# ESO_SENIOR_DESIGN.net
KiCad netlist of a schematic drawn in EAGLE
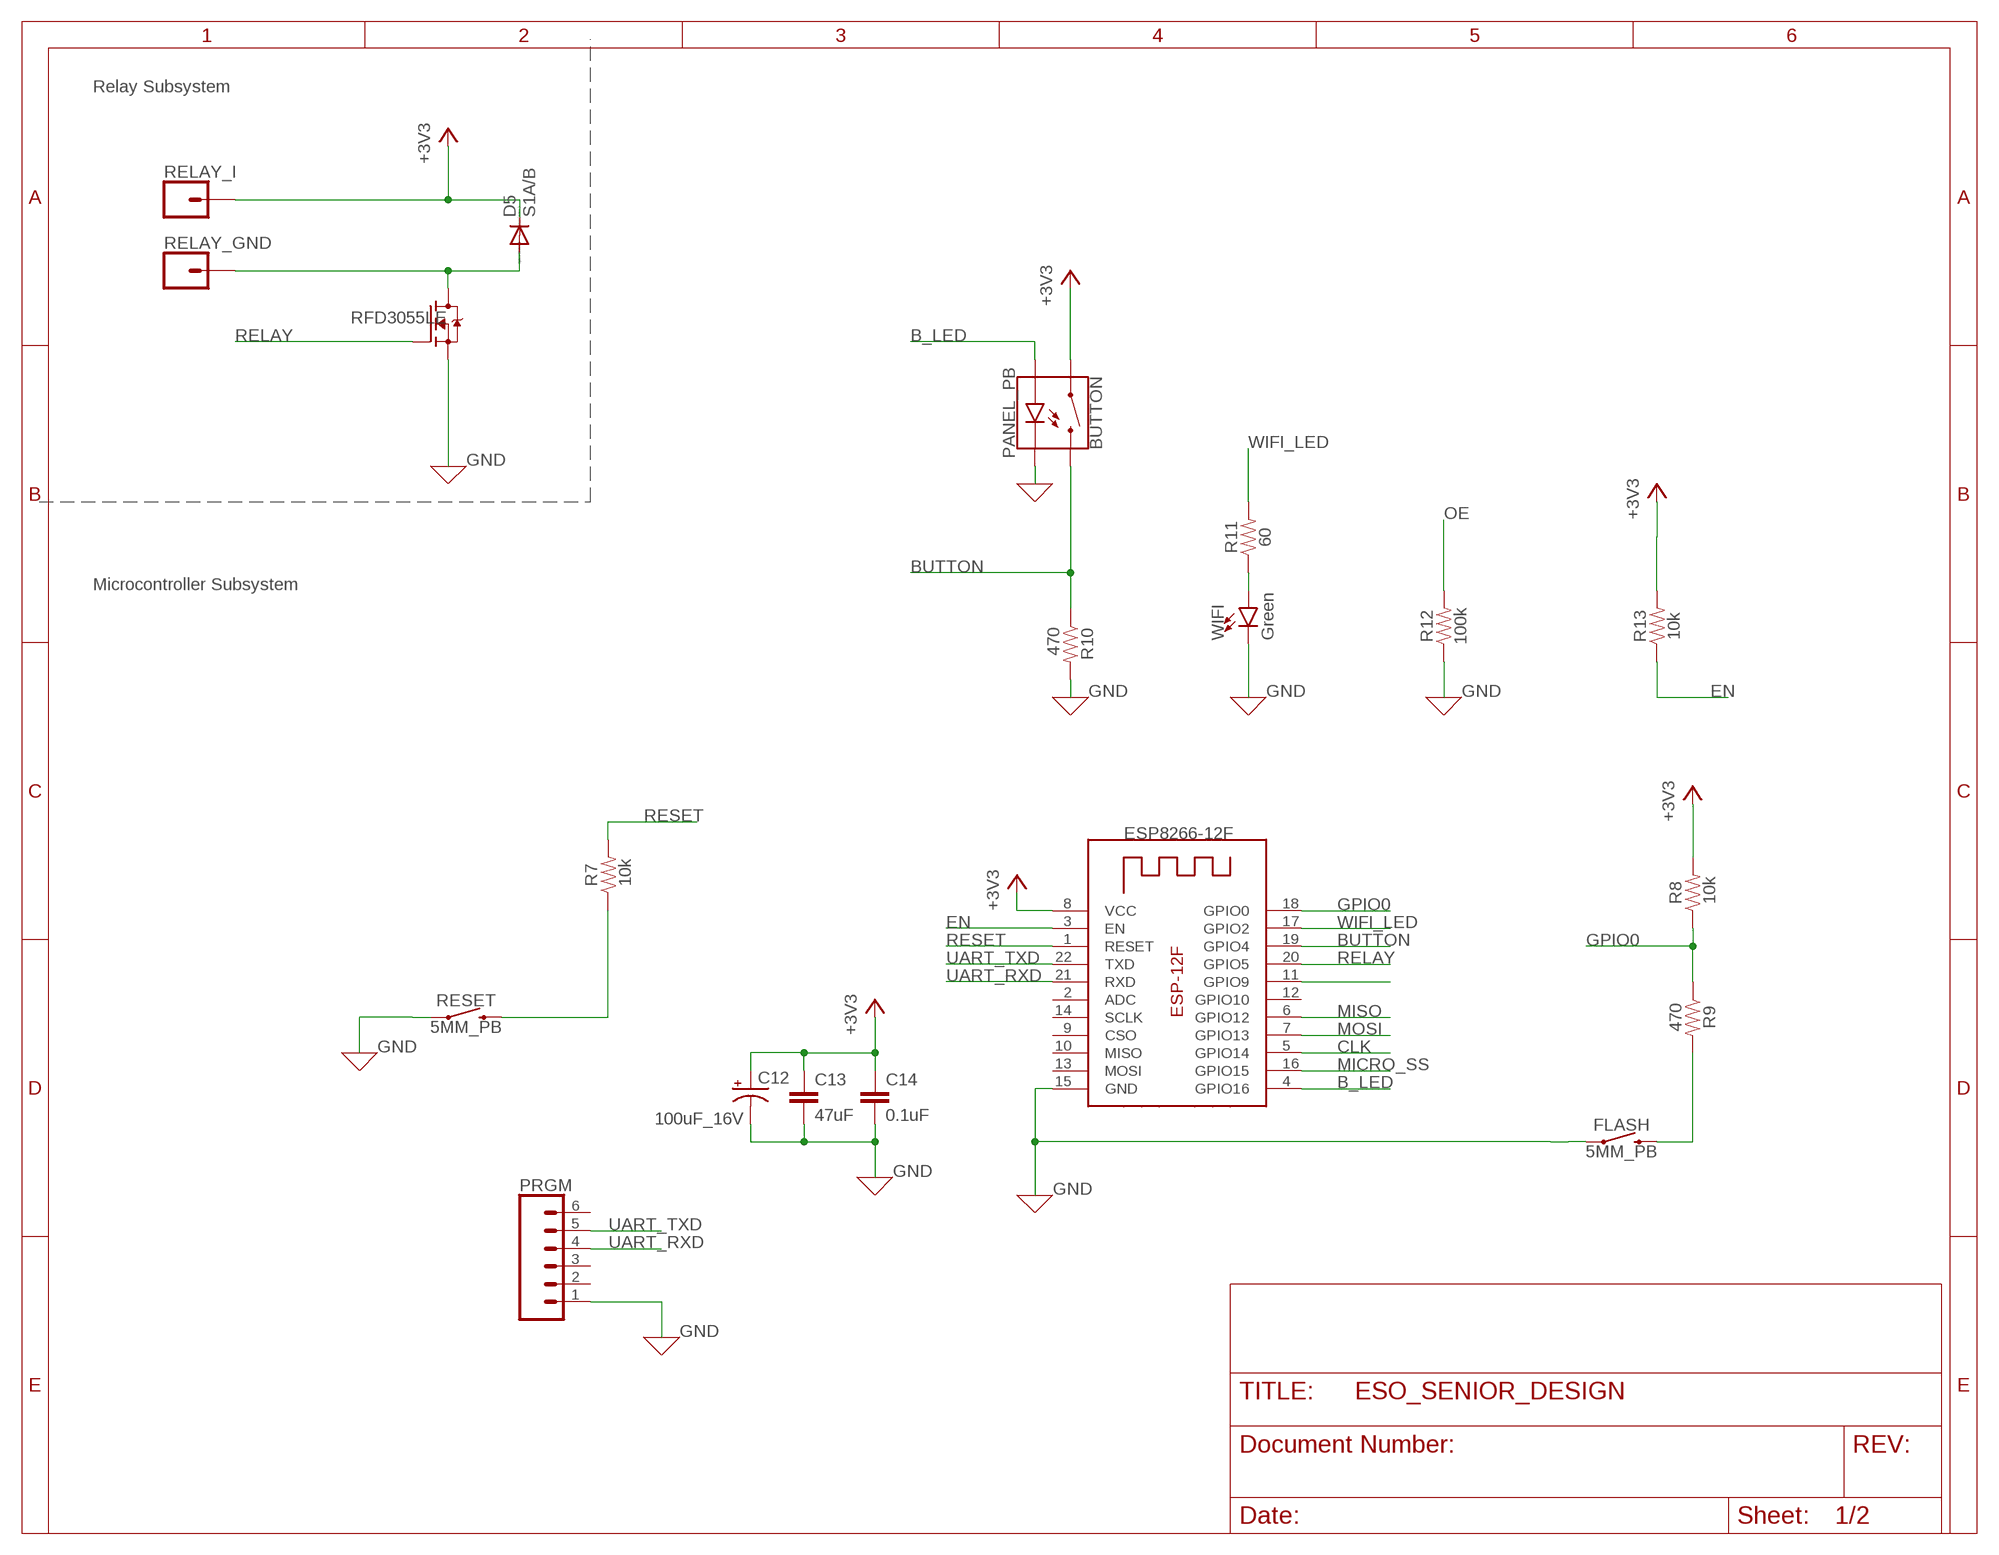
[diagram p0: schematic, sheet 1, part 1 of 2]
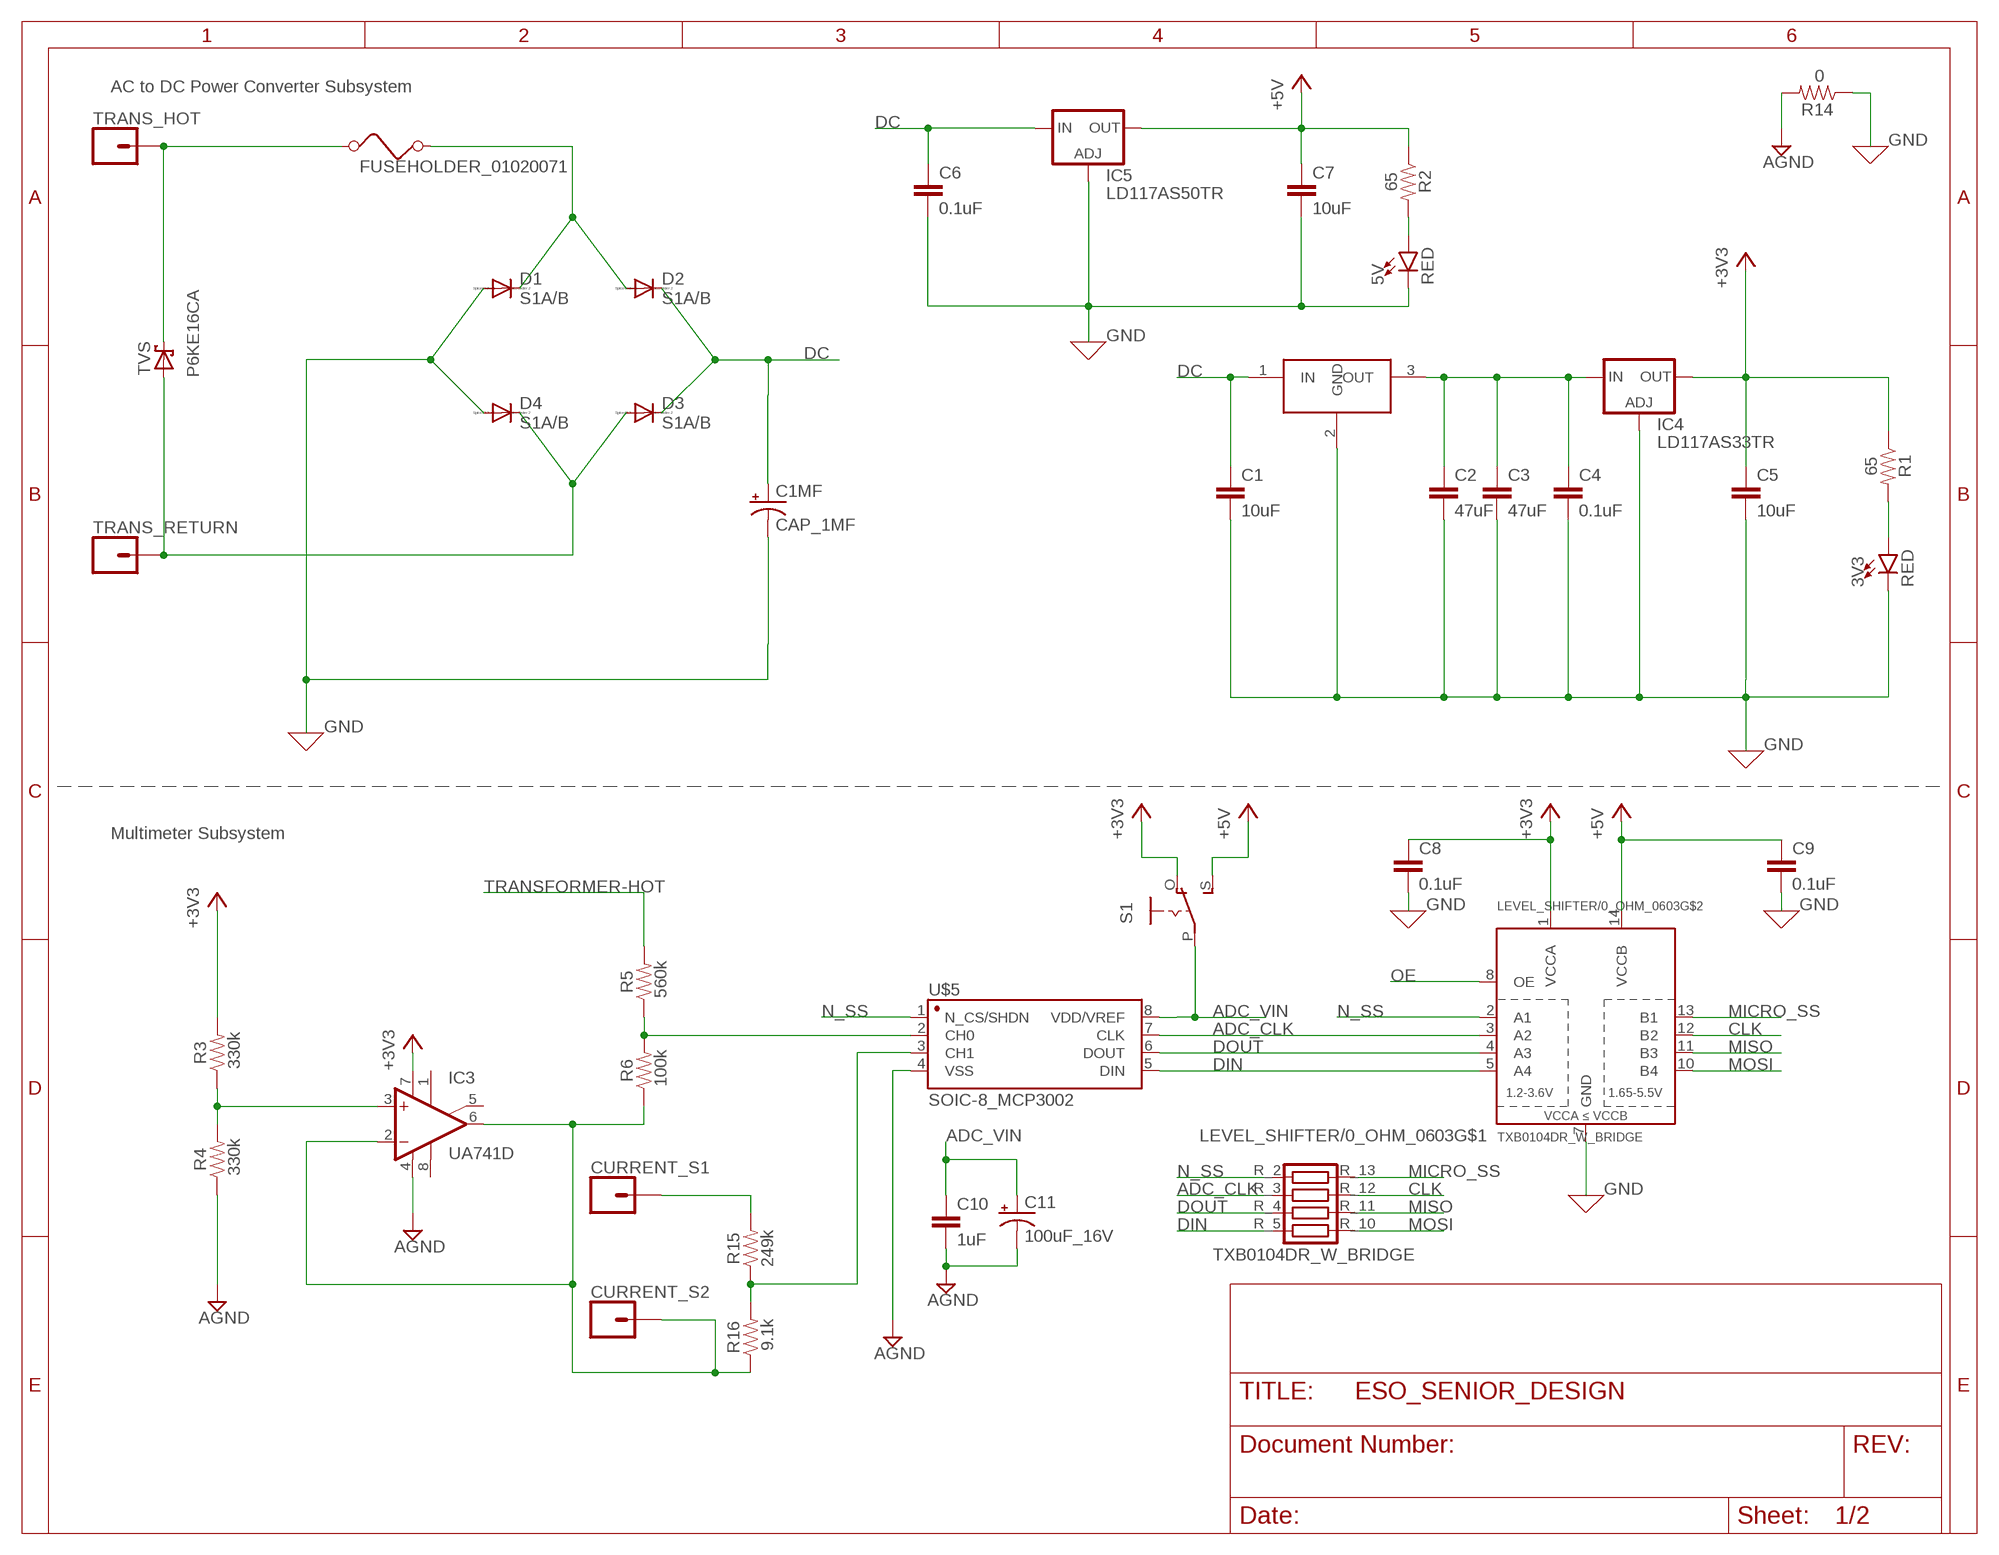
[diagram p1: schematic, sheet 1, part 2 of 2]

(export (version "E")
  (design (tool "Eeschema 10.0.6"))
  (components
    (comp (ref "3V3")
      (value "RED")
      (footprint "eagle-import:LED-1206")
      (libsource (lib "eagle-import") (part "LED1206"))
    )
    (comp (ref "5V")
      (value "RED")
      (footprint "eagle-import:LED-1206")
      (libsource (lib "eagle-import") (part "LED1206"))
    )
    (comp (ref "12F")
      (value "ESP-12F")
      (footprint "eagle-import:ESP-12F")
      (libsource (lib "eagle-import") (part "ESP-12F"))
    )
    (comp (ref "BUTTON")
      (value "PANEL_PB")
      (footprint "eagle-import:PANEL_PB")
      (libsource (lib "eagle-import") (part "PANEL_PB"))
    )
    (comp (ref "C1")
      (value "10uF")
      (footprint "eagle-import:C0805")
      (libsource (lib "eagle-import") (part "C-EUC0805"))
    )
    (comp (ref "C1MF")
      (value "CAP_1MF")
      (footprint "eagle-import:PANASONIC_H13")
      (libsource (lib "eagle-import") (part "CAP_1MF"))
    )
    (comp (ref "C2")
      (value "47uF")
      (footprint "eagle-import:C0805")
      (libsource (lib "eagle-import") (part "C-EUC0805"))
    )
    (comp (ref "C3")
      (value "47uF")
      (footprint "eagle-import:C0805")
      (libsource (lib "eagle-import") (part "C-EUC0805"))
    )
    (comp (ref "C4")
      (value "0.1uF")
      (footprint "eagle-import:C0805")
      (libsource (lib "eagle-import") (part "C-EUC0805"))
    )
    (comp (ref "C5")
      (value "10uF")
      (footprint "eagle-import:C0805")
      (libsource (lib "eagle-import") (part "C-EUC0805"))
    )
    (comp (ref "C6")
      (value "0.1uF")
      (footprint "eagle-import:C0805")
      (libsource (lib "eagle-import") (part "C-EUC0805"))
    )
    (comp (ref "C7")
      (value "10uF")
      (footprint "eagle-import:C0805")
      (libsource (lib "eagle-import") (part "C-EUC0805"))
    )
    (comp (ref "C8")
      (value "0.1uF")
      (footprint "eagle-import:C0805")
      (libsource (lib "eagle-import") (part "C-EUC0805"))
    )
    (comp (ref "C9")
      (value "0.1uF")
      (footprint "eagle-import:C0805")
      (libsource (lib "eagle-import") (part "C-EUC0805"))
    )
    (comp (ref "C10")
      (value "1uF")
      (footprint "eagle-import:C0805")
      (libsource (lib "eagle-import") (part "C-EUC0805"))
    )
    (comp (ref "C11")
      (value "100uF_16V")
      (footprint "eagle-import:PANASONIC_C")
      (libsource (lib "eagle-import") (part "CPOL-USC"))
    )
    (comp (ref "C12")
      (value "100uF_16V")
      (footprint "eagle-import:PANASONIC_C")
      (libsource (lib "eagle-import") (part "CPOL-USC"))
    )
    (comp (ref "C13")
      (value "47uF")
      (footprint "eagle-import:C0805")
      (libsource (lib "eagle-import") (part "C-EUC0805"))
    )
    (comp (ref "C14")
      (value "0.1uF")
      (footprint "eagle-import:C0805")
      (libsource (lib "eagle-import") (part "C-EUC0805"))
    )
    (comp (ref "CURRENT_S1")
      (value "CONN_01")
      (footprint "eagle-import:1X01")
      (libsource (lib "eagle-import") (part "CONN_01"))
    )
    (comp (ref "CURRENT_S2")
      (value "CONN_01")
      (footprint "eagle-import:1X01")
      (libsource (lib "eagle-import") (part "CONN_01"))
    )
    (comp (ref "D1")
      (value "S1A/B")
      (footprint "eagle-import:SMB")
      (libsource (lib "eagle-import") (part "DIODE-SMB"))
    )
    (comp (ref "D2")
      (value "S1A/B")
      (footprint "eagle-import:SMB")
      (libsource (lib "eagle-import") (part "DIODE-SMB"))
    )
    (comp (ref "D3")
      (value "S1A/B")
      (footprint "eagle-import:SMB")
      (libsource (lib "eagle-import") (part "DIODE-SMB"))
    )
    (comp (ref "D4")
      (value "S1A/B")
      (footprint "eagle-import:SMB")
      (libsource (lib "eagle-import") (part "DIODE-SMB"))
    )
    (comp (ref "D5")
      (value "S1A/B")
      (footprint "eagle-import:SMB")
      (libsource (lib "eagle-import") (part "DIODE-SMB"))
    )
    (comp (ref "FLASH")
      (value "5MM_PB")
      (footprint "eagle-import:TACTILE_SWITCH_SMD_5MM")
      (libsource (lib "eagle-import") (part "5MM_PB"))
    )
    (comp (ref "IC3")
      (value "UA741D")
      (footprint "eagle-import:SO08")
      (libsource (lib "eagle-import") (part "741DUA"))
    )
    (comp (ref "IC4")
      (value "LD117AS33TR")
      (footprint "eagle-import:SOT223")
      (libsource (lib "eagle-import") (part "LD117A?S33TR"))
    )
    (comp (ref "IC5")
      (value "LD117AS50TR")
      (footprint "eagle-import:SOT223")
      (libsource (lib "eagle-import") (part "LD117A?S50TR"))
    )
    (comp (ref "LEVEL_SHIFTER/0_OHM_0603")
      (value "TXB0104DR_W_BRIDGE")
      (footprint "eagle-import:SO14")
      (libsource (lib "eagle-import") (part "TXB0104DR_W_BRIDGE"))
    )
    (comp (ref "PRGM")
      (value "CONN_06NO_SILK_FEMALE_PTH")
      (footprint "eagle-import:1X06_NO_SILK")
      (libsource (lib "eagle-import") (part "CONN_06NO_SILK_FEMALE_PTH"))
    )
    (comp (ref "Q$1")
      (value "RFD3055LE")
      (footprint "eagle-import:TO92-SGD")
      (libsource (lib "eagle-import") (part "RFD3055LE"))
    )
    (comp (ref "R1")
      (value "65")
      (footprint "eagle-import:0805")
      (libsource (lib "eagle-import") (part "RESISTOR0805"))
    )
    (comp (ref "R2")
      (value "65")
      (footprint "eagle-import:0805")
      (libsource (lib "eagle-import") (part "RESISTOR0805"))
    )
    (comp (ref "R3")
      (value "330k")
      (footprint "eagle-import:0805")
      (libsource (lib "eagle-import") (part "RESISTOR0805"))
    )
    (comp (ref "R4")
      (value "330k")
      (footprint "eagle-import:0805")
      (libsource (lib "eagle-import") (part "RESISTOR0805"))
    )
    (comp (ref "R5")
      (value "560k")
      (footprint "eagle-import:0805")
      (libsource (lib "eagle-import") (part "RESISTOR0805"))
    )
    (comp (ref "R6")
      (value "100k")
      (footprint "eagle-import:0805")
      (libsource (lib "eagle-import") (part "RESISTOR0805"))
    )
    (comp (ref "R7")
      (value "10k")
      (footprint "eagle-import:0805")
      (libsource (lib "eagle-import") (part "RESISTOR0805"))
    )
    (comp (ref "R8")
      (value "10k")
      (footprint "eagle-import:0805")
      (libsource (lib "eagle-import") (part "RESISTOR0805"))
    )
    (comp (ref "R9")
      (value "470")
      (footprint "eagle-import:0805")
      (libsource (lib "eagle-import") (part "RESISTOR0805"))
    )
    (comp (ref "R10")
      (value "470")
      (footprint "eagle-import:0805")
      (libsource (lib "eagle-import") (part "RESISTOR0805"))
    )
    (comp (ref "R11")
      (value "60")
      (footprint "eagle-import:0805")
      (libsource (lib "eagle-import") (part "RESISTOR0805"))
    )
    (comp (ref "R12")
      (value "100k")
      (footprint "eagle-import:0805")
      (libsource (lib "eagle-import") (part "RESISTOR0805"))
    )
    (comp (ref "R13")
      (value "10k")
      (footprint "eagle-import:0805")
      (libsource (lib "eagle-import") (part "RESISTOR0805"))
    )
    (comp (ref "R14")
      (value "0")
      (footprint "eagle-import:0805")
      (libsource (lib "eagle-import") (part "RESISTOR0805"))
    )
    (comp (ref "R15")
      (value "249k")
      (footprint "eagle-import:0805")
      (libsource (lib "eagle-import") (part "RESISTOR0805"))
    )
    (comp (ref "R16")
      (value "9.1k")
      (footprint "eagle-import:0805")
      (libsource (lib "eagle-import") (part "RESISTOR0805"))
    )
    (comp (ref "RELAY_GND")
      (value "CONN_01")
      (footprint "eagle-import:1X01")
      (libsource (lib "eagle-import") (part "CONN_01"))
    )
    (comp (ref "RELAY_I")
      (value "CONN_01")
      (footprint "eagle-import:1X01")
      (libsource (lib "eagle-import") (part "CONN_01"))
    )
    (comp (ref "RESET")
      (value "5MM_PB")
      (footprint "eagle-import:TACTILE_SWITCH_SMD_5MM")
      (libsource (lib "eagle-import") (part "5MM_PB"))
    )
    (comp (ref "S1")
      (value "EG1218S")
      (footprint "eagle-import:EG1218")
      (libsource (lib "eagle-import") (part "EG1218S"))
    )
    (comp (ref "TRANS_HOT")
      (value "CONN_01")
      (footprint "eagle-import:1X01")
      (libsource (lib "eagle-import") (part "CONN_01"))
    )
    (comp (ref "TRANS_RETURN")
      (value "CONN_01")
      (footprint "eagle-import:1X01")
      (libsource (lib "eagle-import") (part "CONN_01"))
    )
    (comp (ref "TVS")
      (value "1N5819-T")
      (footprint "eagle-import:DO41-7.6")
      (libsource (lib "eagle-import") (part "1N5819-T"))
    )
    (comp (ref "U$1")
      (value "FUSEHOLDER_01020071")
      (footprint "eagle-import:FUSEHOLDER_01020071Z")
      (libsource (lib "eagle-import") (part "FUSEHOLDER_01020071"))
    )
    (comp (ref "U$3")
      (value "BUCK")
      (footprint "eagle-import:TO220H")
      (libsource (lib "eagle-import") (part "BUCK"))
    )
    (comp (ref "U$5")
      (value "SOIC-8_MCP3002")
      (footprint "eagle-import:SO08-0.15")
      (libsource (lib "eagle-import") (part "SOIC-8_MCP3002"))
    )
    (comp (ref "WIFI")
      (value "Green")
      (footprint "eagle-import:LED-1206")
      (libsource (lib "eagle-import") (part "LED1206"))
    )
  )
  (nets
    (net (code "1") (name "+3V3") (class "Default")
      (node (ref "12F") (pin "8") (pinfunction "VCC_8") (pintype "power_in"))
      (node (ref "BUTTON") (pin "1") (pinfunction "1_1") (pintype "passive"))
      (node (ref "C12") (pin "+") (pinfunction "+_+") (pintype "passive"))
      (node (ref "C13") (pin "1") (pinfunction "1_1") (pintype "passive"))
      (node (ref "C14") (pin "1") (pinfunction "1_1") (pintype "passive"))
      (node (ref "C5") (pin "1") (pinfunction "1_1") (pintype "passive"))
      (node (ref "C8") (pin "1") (pinfunction "1_1") (pintype "passive"))
      (node (ref "D5") (pin "C") (pinfunction "C_C") (pintype "passive"))
      (node (ref "IC3") (pin "7") (pinfunction "V+_7") (pintype "power_in"))
      (node (ref "IC4") (pin "2") (pinfunction "OUT_2") (pintype "passive"))
      (node (ref "IC4") (pin "4") (pinfunction "OUT_4") (pintype "passive"))
      (node (ref "LEVEL_SHIFTER/0_OHM_0603") (pin "1") (pinfunction "VCCA_1") (pintype "bidirectional"))
      (node (ref "R1") (pin "1") (pinfunction "1_1") (pintype "passive"))
      (node (ref "R13") (pin "2") (pinfunction "2_2") (pintype "passive"))
      (node (ref "R3") (pin "2") (pinfunction "2_2") (pintype "passive"))
      (node (ref "R8") (pin "2") (pinfunction "2_2") (pintype "passive"))
      (node (ref "RELAY_I") (pin "1") (pinfunction "1_1") (pintype "passive"))
      (node (ref "S1") (pin "O") (pinfunction "O_O") (pintype "passive"))
    )
    (net (code "2") (name "+5V") (class "Default")
      (node (ref "C7") (pin "1") (pinfunction "1_1") (pintype "passive"))
      (node (ref "C9") (pin "1") (pinfunction "1_1") (pintype "passive"))
      (node (ref "IC5") (pin "2") (pinfunction "OUT_2") (pintype "passive"))
      (node (ref "IC5") (pin "4") (pinfunction "OUT_4") (pintype "passive"))
      (node (ref "LEVEL_SHIFTER/0_OHM_0603") (pin "14") (pinfunction "VCCB_14") (pintype "bidirectional"))
      (node (ref "R2") (pin "1") (pinfunction "1_1") (pintype "passive"))
      (node (ref "S1") (pin "S") (pinfunction "S_S") (pintype "passive"))
    )
    (net (code "3") (name "ADC_CLK") (class "Default")
      (node (ref "LEVEL_SHIFTER/0_OHM_0603") (pin "3") (pinfunction "A2_3") (pintype "bidirectional"))
      (node (ref "LEVEL_SHIFTER/0_OHM_0603") (pin "R_3") (pinfunction "2_R_3") (pintype "passive"))
      (node (ref "U$5") (pin "7") (pinfunction "CLK_7") (pintype "bidirectional"))
    )
    (net (code "4") (name "ADC_VIN") (class "Default")
      (node (ref "C10") (pin "1") (pinfunction "1_1") (pintype "passive"))
      (node (ref "C11") (pin "+") (pinfunction "+_+") (pintype "passive"))
      (node (ref "S1") (pin "P") (pinfunction "P_P") (pintype "passive"))
      (node (ref "U$5") (pin "8") (pinfunction "VDD/VREF_8") (pintype "bidirectional"))
    )
    (net (code "5") (name "AGND") (class "Default")
      (node (ref "C10") (pin "2") (pinfunction "2_2") (pintype "passive"))
      (node (ref "C11") (pin "-") (pinfunction "-_-") (pintype "passive"))
      (node (ref "IC3") (pin "4") (pinfunction "V-_4") (pintype "power_in"))
      (node (ref "R14") (pin "2") (pinfunction "2_2") (pintype "passive"))
      (node (ref "R4") (pin "1") (pinfunction "1_1") (pintype "passive"))
      (node (ref "U$5") (pin "4") (pinfunction "VSS_4") (pintype "bidirectional"))
    )
    (net (code "6") (name "BUTTON") (class "Default")
      (node (ref "12F") (pin "19") (pinfunction "GPIO4_19") (pintype "bidirectional"))
      (node (ref "BUTTON") (pin "2") (pinfunction "2_2") (pintype "passive"))
      (node (ref "R10") (pin "1") (pinfunction "1_1") (pintype "passive"))
    )
    (net (code "7") (name "B_LED") (class "Default")
      (node (ref "12F") (pin "4") (pinfunction "GPIO16_4") (pintype "bidirectional"))
      (node (ref "BUTTON") (pin "3") (pinfunction "A_3") (pintype "passive"))
    )
    (net (code "8") (name "CLK") (class "Default")
      (node (ref "12F") (pin "5") (pinfunction "GPIO14_5") (pintype "bidirectional"))
      (node (ref "LEVEL_SHIFTER/0_OHM_0603") (pin "12") (pinfunction "B2_12") (pintype "bidirectional"))
      (node (ref "LEVEL_SHIFTER/0_OHM_0603") (pin "R_12") (pinfunction "7_R_12") (pintype "passive"))
    )
    (net (code "9") (name "DC") (class "Default")
      (node (ref "C1") (pin "1") (pinfunction "1_1") (pintype "passive"))
      (node (ref "C1MF") (pin "+") (pinfunction "+_+") (pintype "passive"))
      (node (ref "C6") (pin "1") (pinfunction "1_1") (pintype "passive"))
      (node (ref "D2") (pin "C") (pinfunction "C_C") (pintype "passive"))
      (node (ref "D3") (pin "C") (pinfunction "C_C") (pintype "passive"))
      (node (ref "IC5") (pin "3") (pinfunction "IN_3") (pintype "input"))
      (node (ref "U$3") (pin "1") (pinfunction "IN_1") (pintype "bidirectional"))
    )
    (net (code "10") (name "DIN") (class "Default")
      (node (ref "LEVEL_SHIFTER/0_OHM_0603") (pin "5") (pinfunction "A4_5") (pintype "bidirectional"))
      (node (ref "LEVEL_SHIFTER/0_OHM_0603") (pin "R_5") (pinfunction "4_R_5") (pintype "passive"))
      (node (ref "U$5") (pin "5") (pinfunction "DIN_5") (pintype "bidirectional"))
    )
    (net (code "11") (name "DOUT") (class "Default")
      (node (ref "LEVEL_SHIFTER/0_OHM_0603") (pin "4") (pinfunction "A3_4") (pintype "bidirectional"))
      (node (ref "LEVEL_SHIFTER/0_OHM_0603") (pin "R_4") (pinfunction "3_R_4") (pintype "passive"))
      (node (ref "U$5") (pin "6") (pinfunction "DOUT_6") (pintype "bidirectional"))
    )
    (net (code "12") (name "EN") (class "Default")
      (node (ref "12F") (pin "3") (pinfunction "EN_3") (pintype "input"))
      (node (ref "R13") (pin "1") (pinfunction "1_1") (pintype "passive"))
    )
    (net (code "13") (name "GND") (class "Default")
      (node (ref "12F") (pin "15") (pinfunction "GND_15") (pintype "power_in"))
      (node (ref "3V3") (pin "C") (pinfunction "C_C") (pintype "passive"))
      (node (ref "5V") (pin "C") (pinfunction "C_C") (pintype "passive"))
      (node (ref "BUTTON") (pin "4") (pinfunction "C_4") (pintype "passive"))
      (node (ref "C1") (pin "2") (pinfunction "2_2") (pintype "passive"))
      (node (ref "C12") (pin "-") (pinfunction "-_-") (pintype "passive"))
      (node (ref "C13") (pin "2") (pinfunction "2_2") (pintype "passive"))
      (node (ref "C14") (pin "2") (pinfunction "2_2") (pintype "passive"))
      (node (ref "C1MF") (pin "-") (pinfunction "-_-") (pintype "passive"))
      (node (ref "C2") (pin "2") (pinfunction "2_2") (pintype "passive"))
      (node (ref "C3") (pin "2") (pinfunction "2_2") (pintype "passive"))
      (node (ref "C4") (pin "2") (pinfunction "2_2") (pintype "passive"))
      (node (ref "C5") (pin "2") (pinfunction "2_2") (pintype "passive"))
      (node (ref "C6") (pin "2") (pinfunction "2_2") (pintype "passive"))
      (node (ref "C7") (pin "2") (pinfunction "2_2") (pintype "passive"))
      (node (ref "C8") (pin "2") (pinfunction "2_2") (pintype "passive"))
      (node (ref "C9") (pin "2") (pinfunction "2_2") (pintype "passive"))
      (node (ref "D1") (pin "A") (pinfunction "A_A") (pintype "passive"))
      (node (ref "D4") (pin "A") (pinfunction "A_A") (pintype "passive"))
      (node (ref "FLASH") (pin "1") (pinfunction "1_1") (pintype "passive"))
      (node (ref "FLASH") (pin "3") (pinfunction "1_3") (pintype "passive"))
      (node (ref "IC4") (pin "1") (pinfunction "ADJ_1") (pintype "input"))
      (node (ref "IC5") (pin "1") (pinfunction "ADJ_1") (pintype "input"))
      (node (ref "LEVEL_SHIFTER/0_OHM_0603") (pin "7") (pinfunction "GND_7") (pintype "bidirectional"))
      (node (ref "PRGM") (pin "1") (pinfunction "1_1") (pintype "passive"))
      (node (ref "Q$1") (pin "S") (pinfunction "S_S") (pintype "passive"))
      (node (ref "R10") (pin "2") (pinfunction "2_2") (pintype "passive"))
      (node (ref "R12") (pin "1") (pinfunction "1_1") (pintype "passive"))
      (node (ref "R14") (pin "1") (pinfunction "1_1") (pintype "passive"))
      (node (ref "RESET") (pin "1") (pinfunction "1_1") (pintype "passive"))
      (node (ref "RESET") (pin "3") (pinfunction "1_3") (pintype "passive"))
      (node (ref "U$3") (pin "2") (pinfunction "GND_2") (pintype "bidirectional"))
      (node (ref "WIFI") (pin "C") (pinfunction "C_C") (pintype "passive"))
    )
    (net (code "14") (name "GPIO0") (class "Default")
      (node (ref "12F") (pin "18") (pinfunction "GPIO0_18") (pintype "bidirectional"))
      (node (ref "R8") (pin "1") (pinfunction "1_1") (pintype "passive"))
      (node (ref "R9") (pin "1") (pinfunction "1_1") (pintype "passive"))
    )
    (net (code "15") (name "MICRO_SS") (class "Default")
      (node (ref "12F") (pin "16") (pinfunction "GPIO15_16") (pintype "bidirectional"))
      (node (ref "LEVEL_SHIFTER/0_OHM_0603") (pin "13") (pinfunction "B1_13") (pintype "bidirectional"))
      (node (ref "LEVEL_SHIFTER/0_OHM_0603") (pin "R_13") (pinfunction "8_R_13") (pintype "passive"))
    )
    (net (code "16") (name "MISO") (class "Default")
      (node (ref "12F") (pin "6") (pinfunction "GPIO12_6") (pintype "bidirectional"))
      (node (ref "LEVEL_SHIFTER/0_OHM_0603") (pin "11") (pinfunction "B3_11") (pintype "bidirectional"))
      (node (ref "LEVEL_SHIFTER/0_OHM_0603") (pin "R_11") (pinfunction "6_R_11") (pintype "passive"))
    )
    (net (code "17") (name "MOSI") (class "Default")
      (node (ref "12F") (pin "7") (pinfunction "GPIO13_7") (pintype "bidirectional"))
      (node (ref "LEVEL_SHIFTER/0_OHM_0603") (pin "10") (pinfunction "B4_10") (pintype "bidirectional"))
      (node (ref "LEVEL_SHIFTER/0_OHM_0603") (pin "R_10") (pinfunction "5_R_10") (pintype "passive"))
    )
    (net (code "18") (name "N_SS") (class "Default")
      (node (ref "LEVEL_SHIFTER/0_OHM_0603") (pin "2") (pinfunction "A1_2") (pintype "bidirectional"))
      (node (ref "LEVEL_SHIFTER/0_OHM_0603") (pin "R_2") (pinfunction "1_R_2") (pintype "passive"))
      (node (ref "U$5") (pin "1") (pinfunction "N_CS/SHDN_1") (pintype "bidirectional"))
    )
    (net (code "19") (name "Net-(3V3-PadA)") (class "Default")
      (node (ref "3V3") (pin "A") (pinfunction "A_A") (pintype "passive"))
      (node (ref "R1") (pin "2") (pinfunction "2_2") (pintype "passive"))
    )
    (net (code "20") (name "Net-(5V-PadA)") (class "Default")
      (node (ref "5V") (pin "A") (pinfunction "A_A") (pintype "passive"))
      (node (ref "R2") (pin "2") (pinfunction "2_2") (pintype "passive"))
    )
    (net (code "21") (name "Net-(CURRENT_S1-Pad1)") (class "Default")
      (node (ref "CURRENT_S1") (pin "1") (pinfunction "1_1") (pintype "passive"))
      (node (ref "R15") (pin "2") (pinfunction "2_2") (pintype "passive"))
    )
    (net (code "22") (name "Net-(D3-PadA)") (class "Default")
      (node (ref "D3") (pin "A") (pinfunction "A_A") (pintype "passive"))
      (node (ref "D4") (pin "C") (pinfunction "C_C") (pintype "passive"))
      (node (ref "TRANS_RETURN") (pin "1") (pinfunction "1_1") (pintype "passive"))
      (node (ref "TVS") (pin "A") (pinfunction "A_A") (pintype "passive"))
    )
    (net (code "23") (name "Net-(D5-PadA)") (class "Default")
      (node (ref "D5") (pin "A") (pinfunction "A_A") (pintype "passive"))
      (node (ref "Q$1") (pin "D") (pinfunction "D_D") (pintype "passive"))
      (node (ref "RELAY_GND") (pin "1") (pinfunction "1_1") (pintype "passive"))
    )
    (net (code "24") (name "Net-(FLASH-2-Pad4)") (class "Default")
      (node (ref "FLASH") (pin "2") (pinfunction "2_2") (pintype "passive"))
      (node (ref "FLASH") (pin "4") (pinfunction "2_4") (pintype "passive"))
      (node (ref "R9") (pin "2") (pinfunction "2_2") (pintype "passive"))
    )
    (net (code "25") (name "Net-(IC3-+IN)") (class "Default")
      (node (ref "IC3") (pin "3") (pinfunction "+IN_3") (pintype "input"))
      (node (ref "R3") (pin "1") (pinfunction "1_1") (pintype "passive"))
      (node (ref "R4") (pin "2") (pinfunction "2_2") (pintype "passive"))
    )
    (net (code "26") (name "Net-(IC3--IN)") (class "Default")
      (node (ref "CURRENT_S2") (pin "1") (pinfunction "1_1") (pintype "passive"))
      (node (ref "IC3") (pin "2") (pinfunction "-IN_2") (pintype "input"))
      (node (ref "IC3") (pin "6") (pinfunction "OUT_6") (pintype "output"))
      (node (ref "R16") (pin "1") (pinfunction "1_1") (pintype "passive"))
      (node (ref "R6") (pin "1") (pinfunction "1_1") (pintype "passive"))
    )
    (net (code "27") (name "Net-(IC4-IN)") (class "Default")
      (node (ref "C2") (pin "1") (pinfunction "1_1") (pintype "passive"))
      (node (ref "C3") (pin "1") (pinfunction "1_1") (pintype "passive"))
      (node (ref "C4") (pin "1") (pinfunction "1_1") (pintype "passive"))
      (node (ref "IC4") (pin "3") (pinfunction "IN_3") (pintype "input"))
      (node (ref "U$3") (pin "3") (pinfunction "OUT_3") (pintype "bidirectional"))
    )
    (net (code "28") (name "Net-(R7-Pad1)") (class "Default")
      (node (ref "R7") (pin "1") (pinfunction "1_1") (pintype "passive"))
      (node (ref "RESET") (pin "2") (pinfunction "2_2") (pintype "passive"))
      (node (ref "RESET") (pin "4") (pinfunction "2_4") (pintype "passive"))
    )
    (net (code "29") (name "Net-(R11-Pad1)") (class "Default")
      (node (ref "R11") (pin "1") (pinfunction "1_1") (pintype "passive"))
      (node (ref "WIFI") (pin "A") (pinfunction "A_A") (pintype "passive"))
    )
    (net (code "30") (name "Net-(U$1-2)") (class "Default")
      (node (ref "D1") (pin "C") (pinfunction "C_C") (pintype "passive"))
      (node (ref "D2") (pin "A") (pinfunction "A_A") (pintype "passive"))
      (node (ref "U$1") (pin "P$3") (pinfunction "2_P$3") (pintype "passive"))
    )
    (net (code "31") (name "Net-(U$5-CH0)") (class "Default")
      (node (ref "R5") (pin "1") (pinfunction "1_1") (pintype "passive"))
      (node (ref "R6") (pin "2") (pinfunction "2_2") (pintype "passive"))
      (node (ref "U$5") (pin "2") (pinfunction "CH0_2") (pintype "bidirectional"))
    )
    (net (code "32") (name "Net-(U$5-CH1)") (class "Default")
      (node (ref "R15") (pin "1") (pinfunction "1_1") (pintype "passive"))
      (node (ref "R16") (pin "2") (pinfunction "2_2") (pintype "passive"))
      (node (ref "U$5") (pin "3") (pinfunction "CH1_3") (pintype "bidirectional"))
    )
    (net (code "33") (name "OE") (class "Default")
      (node (ref "12F") (pin "11") (pinfunction "GPIO9_11") (pintype "bidirectional"))
      (node (ref "LEVEL_SHIFTER/0_OHM_0603") (pin "8") (pinfunction "OE_8") (pintype "bidirectional"))
      (node (ref "R12") (pin "2") (pinfunction "2_2") (pintype "passive"))
    )
    (net (code "34") (name "RELAY") (class "Default")
      (node (ref "12F") (pin "20") (pinfunction "GPIO5_20") (pintype "bidirectional"))
      (node (ref "Q$1") (pin "G") (pinfunction "G_G") (pintype "passive"))
    )
    (net (code "35") (name "RESET") (class "Default")
      (node (ref "12F") (pin "1") (pinfunction "RESET_1") (pintype "input"))
      (node (ref "R7") (pin "2") (pinfunction "2_2") (pintype "passive"))
    )
    (net (code "36") (name "TRANSFORMER-HOT") (class "Default")
      (node (ref "R5") (pin "2") (pinfunction "2_2") (pintype "passive"))
      (node (ref "TRANS_HOT") (pin "1") (pinfunction "1_1") (pintype "passive"))
      (node (ref "TVS") (pin "C") (pinfunction "C_C") (pintype "passive"))
      (node (ref "U$1") (pin "P$1") (pinfunction "1_P$1") (pintype "passive"))
    )
    (net (code "37") (name "UART_RXD") (class "Default")
      (node (ref "12F") (pin "21") (pinfunction "RXD_21") (pintype "input"))
      (node (ref "PRGM") (pin "4") (pinfunction "4_4") (pintype "passive"))
    )
    (net (code "38") (name "UART_TXD") (class "Default")
      (node (ref "12F") (pin "22") (pinfunction "TXD_22") (pintype "output"))
      (node (ref "PRGM") (pin "5") (pinfunction "5_5") (pintype "passive"))
    )
    (net (code "39") (name "WIFI_LED") (class "Default")
      (node (ref "12F") (pin "17") (pinfunction "GPIO2_17") (pintype "bidirectional"))
      (node (ref "R11") (pin "2") (pinfunction "2_2") (pintype "passive"))
    )
    (net (code "40") (name "unconnected-(12F-ADC-Pad2)") (class "Default")
      (node (ref "12F") (pin "2") (pinfunction "ADC_2") (pintype "input"))
    )
    (net (code "41") (name "unconnected-(12F-CSO-Pad9)") (class "Default")
      (node (ref "12F") (pin "9") (pinfunction "CSO_9") (pintype "bidirectional"))
    )
    (net (code "42") (name "unconnected-(12F-GPIO10-Pad12)") (class "Default")
      (node (ref "12F") (pin "12") (pinfunction "GPIO10_12") (pintype "bidirectional"))
    )
    (net (code "43") (name "unconnected-(12F-MISO-Pad10)") (class "Default")
      (node (ref "12F") (pin "10") (pinfunction "MISO_10") (pintype "input"))
    )
    (net (code "44") (name "unconnected-(12F-MOSI-Pad13)") (class "Default")
      (node (ref "12F") (pin "13") (pinfunction "MOSI_13") (pintype "output"))
    )
    (net (code "45") (name "unconnected-(12F-SCLK-Pad14)") (class "Default")
      (node (ref "12F") (pin "14") (pinfunction "SCLK_14") (pintype "bidirectional"))
    )
    (net (code "46") (name "unconnected-(IC3-ON1-Pad1)") (class "Default")
      (node (ref "IC3") (pin "1") (pinfunction "ON1_1") (pintype "passive"))
    )
    (net (code "47") (name "unconnected-(IC3-ON2-Pad5)") (class "Default")
      (node (ref "IC3") (pin "5") (pinfunction "ON2_5") (pintype "passive"))
    )
    (net (code "48") (name "unconnected-(IC3-OPT-Pad8)") (class "Default")
      (node (ref "IC3") (pin "8") (pinfunction "OPT_8") (pintype "passive"))
    )
    (net (code "49") (name "unconnected-(PRGM-Pad2)") (class "Default")
      (node (ref "PRGM") (pin "2") (pinfunction "2_2") (pintype "passive"))
    )
    (net (code "50") (name "unconnected-(PRGM-Pad3)") (class "Default")
      (node (ref "PRGM") (pin "3") (pinfunction "3_3") (pintype "passive"))
    )
    (net (code "51") (name "unconnected-(PRGM-Pad6)") (class "Default")
      (node (ref "PRGM") (pin "6") (pinfunction "6_6") (pintype "passive"))
    )
  )
)
